# Sheet1.net
KiCad netlist of a schematic drawn in Altium Designer
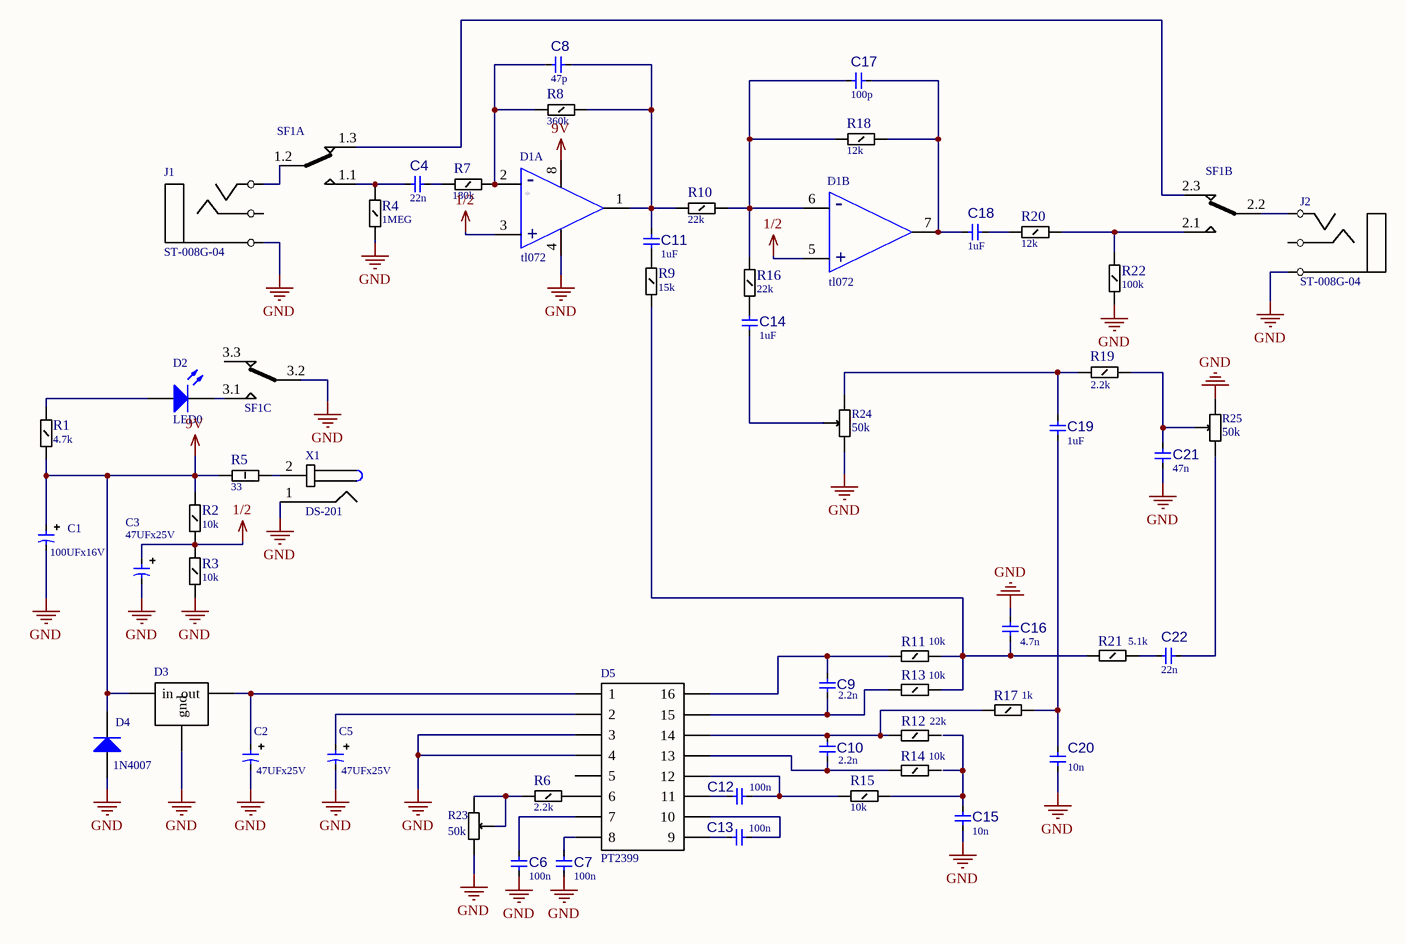
[diagram p0: Sheet1.SchDoc]

(export (version "E")
  (design (tool "Eeschema 10.0.6"))
  (components
    (comp (ref "C1")
      (value "100UFx16V")
      (footprint "C12x5")
      (fields (field (name "PART NUMBER") "Condensator C12x8") (field (name "Comment") "C15x8"))
      (libsource (lib "Database_Libs") (part "C15x8"))
    )
    (comp (ref "C2")
      (value "47UFx25V")
      (footprint "B41828_D5")
      (fields
        (field (name "PART NUMBER") "Condensator B41851")
        (field (name "MANUFACTURER") "Epcos")
        (field (name "Comment") "C15x8")
      )
      (libsource (lib "Database_Libs") (part "C15x8"))
    )
    (comp (ref "C3")
      (value "47UFx25V")
      (footprint "B41828_D5")
      (fields
        (field (name "PART NUMBER") "Condensator B41851")
        (field (name "MANUFACTURER") "Epcos")
        (field (name "Comment") "C15x8")
      )
      (libsource (lib "Database_Libs") (part "C15x8"))
    )
    (comp (ref "C4")
      (value "22n")
      (footprint "B32529C 3222")
      (fields
        (field (name "PART NUMBER") "Condensator C22n")
        (field (name "MANUFACTURERPARTNUMBER") "B32529C1223J000")
        (field (name "Comment") "C0603")
      )
      (libsource (lib "Database_Libs") (part "C0603"))
    )
    (comp (ref "C5")
      (value "47UFx25V")
      (footprint "B41828_D5")
      (fields
        (field (name "PART NUMBER") "Condensator B41851")
        (field (name "MANUFACTURER") "Epcos")
        (field (name "Comment") "C15x8")
      )
      (libsource (lib "Database_Libs") (part "C15x8"))
    )
    (comp (ref "C6")
      (value "100n")
      (footprint "B32529C 3222")
      (fields
        (field (name "PART NUMBER") "Condensator C100n")
        (field (name "MANUFACTURER") "Epcos")
        (field (name "MANUFACTURERPARTNUMBER") "B32529C1223J000")
      )
      (libsource (lib "Database_Libs") (part "C0603"))
    )
    (comp (ref "C7")
      (value "100n")
      (footprint "B32529C 3222")
      (fields
        (field (name "PART NUMBER") "Condensator C100n")
        (field (name "MANUFACTURER") "Epcos")
        (field (name "MANUFACTURERPARTNUMBER") "B32529C1223J000")
      )
      (libsource (lib "Database_Libs") (part "C0603"))
    )
    (comp (ref "C8")
      (value "47p")
      (footprint "C1206")
      (fields (field (name "PART NUMBER") "Condensator 1206 100") (field (name "Comment") "C1206"))
      (libsource (lib "Database_Libs") (part "C1206"))
    )
    (comp (ref "C9")
      (value "2.2n")
      (footprint "B32529C 3222")
      (fields
        (field (name "PART NUMBER") "Condensator C2.2n")
        (field (name "MANUFACTURER") "Китай")
        (field (name "MANUFACTURERPARTNUMBER") "К73-17")
      )
      (libsource (lib "Database_Libs") (part "C0603"))
    )
    (comp (ref "C10")
      (value "2.2n")
      (footprint "B32529C 3222")
      (fields
        (field (name "PART NUMBER") "Condensator C2.2n")
        (field (name "MANUFACTURER") "Китай")
        (field (name "MANUFACTURERPARTNUMBER") "К73-17")
      )
      (libsource (lib "Database_Libs") (part "C0603"))
    )
    (comp (ref "C11")
      (value "1uF")
      (footprint "B32529_C0105")
      (fields
        (field (name "PART NUMBER") "Condensator 1u")
        (field (name "MANUFACTURER") "Epcos")
        (field (name "MANUFACTURERPARTNUMBER") "B32529C0105K000")
      )
      (libsource (lib "Database_Libs") (part "C0603"))
    )
    (comp (ref "C12")
      (value "100n")
      (footprint "B32529C 3222")
      (fields
        (field (name "PART NUMBER") "Condensator C100n")
        (field (name "MANUFACTURER") "Epcos")
        (field (name "MANUFACTURERPARTNUMBER") "B32529C1223J000")
      )
      (libsource (lib "Database_Libs") (part "C0603"))
    )
    (comp (ref "C13")
      (value "100n")
      (footprint "B32529C 3222")
      (fields
        (field (name "PART NUMBER") "Condensator C100n")
        (field (name "MANUFACTURER") "Epcos")
        (field (name "MANUFACTURERPARTNUMBER") "B32529C1223J000")
      )
      (libsource (lib "Database_Libs") (part "C0603"))
    )
    (comp (ref "C14")
      (value "1uF")
      (footprint "B32529_C0105")
      (fields
        (field (name "PART NUMBER") "Condensator 1u")
        (field (name "MANUFACTURER") "Epcos")
        (field (name "MANUFACTURERPARTNUMBER") "B32529C0105K000")
      )
      (libsource (lib "Database_Libs") (part "C0603"))
    )
    (comp (ref "C15")
      (value "10n")
      (footprint "B32529C 3222")
      (fields (field (name "PART NUMBER") "Condensator C10n"))
      (libsource (lib "Database_Libs") (part "C0603"))
    )
    (comp (ref "C16")
      (value "4.7n")
      (footprint "B32529C 3222")
      (fields
        (field (name "PART NUMBER") "Condensator C4.7n")
        (field (name "MANUFACTURER") "Китай")
        (field (name "MANUFACTURERPARTNUMBER") "К73-17")
      )
      (libsource (lib "Database_Libs") (part "C0603"))
    )
    (comp (ref "C17")
      (value "100p")
      (footprint "C1206")
      (fields (field (name "PART NUMBER") "Condensator 1206 100") (field (name "Comment") "C1206"))
      (libsource (lib "Database_Libs") (part "C1206"))
    )
    (comp (ref "C18")
      (value "1uF")
      (footprint "B32529_C0105")
      (fields
        (field (name "PART NUMBER") "Condensator 1u")
        (field (name "MANUFACTURER") "Epcos")
        (field (name "MANUFACTURERPARTNUMBER") "B32529C0105K000")
      )
      (libsource (lib "Database_Libs") (part "C0603"))
    )
    (comp (ref "C19")
      (value "1uF")
      (footprint "B32529_C0105")
      (fields
        (field (name "PART NUMBER") "Condensator 1u")
        (field (name "MANUFACTURER") "Epcos")
        (field (name "MANUFACTURERPARTNUMBER") "B32529C0105K000")
      )
      (libsource (lib "Database_Libs") (part "C0603"))
    )
    (comp (ref "C20")
      (value "10n")
      (footprint "B32529C 3222")
      (fields (field (name "PART NUMBER") "Condensator C10n"))
      (libsource (lib "Database_Libs") (part "C0603"))
    )
    (comp (ref "C21")
      (value "47n")
      (footprint "B32529C 3222")
      (fields
        (field (name "PART NUMBER") "Condensator C47n")
        (field (name "MANUFACTURER") "Epcos")
        (field (name "MANUFACTURERPARTNUMBER") "B32529C1473J000")
      )
      (libsource (lib "Database_Libs") (part "C0603"))
    )
    (comp (ref "C22")
      (value "22n")
      (footprint "B32529C 3222")
      (fields
        (field (name "PART NUMBER") "Condensator C22n")
        (field (name "MANUFACTURERPARTNUMBER") "B32529C1223J000")
        (field (name "Comment") "C0603")
      )
      (libsource (lib "Database_Libs") (part "C0603"))
    )
    (comp (ref "D1") (value "tl072") (footprint "SO8_L") (libsource (lib "Database_Libs") (part "tl072")))
    (comp (ref "D2")
      (value "LED0")
      (footprint "LED-0")
      (description "Typical INFRARED GaAs LED")
      (fields (field (name "PUBLISHER") "Altium Limited"))
      (libsource (lib "Miscellaneous Devices") (part "LED0"))
    )
    (comp (ref "D3")
      (value "L7805")
      (footprint "D2PACK")
      (fields (field (name "MANUFACTURERPARTNUMBER") "L7805ABD2T-TR"))
      (libsource (lib "Database_Libs") (part "L7805"))
    )
    (comp (ref "D4")
      (value "1N4007")
      (footprint "DO-41")
      (description "1 Amp General Purpose Rectifier")
      (fields (field (name "PUBLISHER") "Altium Limited"))
      (libsource (lib "Miscellaneous Devices") (part "Diode 1N4007"))
    )
    (comp (ref "D5")
      (value "PT2399")
      (footprint "DIP-16")
      (fields (field (name "MANUFACTURER") "Princeton Technology"))
      (libsource (lib "Database_Libs") (part "PT2399"))
    )
    (comp (ref "J1")
      (value "ST-008G-04")
      (footprint "ST-008G-04")
      (libsource (lib "Database_Libs") (part "ST-008G-04"))
    )
    (comp (ref "J2")
      (value "ST-008G-04")
      (footprint "ST-008G-04")
      (libsource (lib "Database_Libs") (part "ST-008G-04"))
    )
    (comp (ref "R1")
      (value "4.7k")
      (footprint "R1206")
      (fields (field (name "PART NUMBER") "Resistor 1206 1.5k") (field (name "Comment") "R1206-0,25 W"))
      (libsource (lib "Database_Libs") (part "R1206-0,25 W"))
    )
    (comp (ref "R2")
      (value "10k")
      (footprint "R1206")
      (fields (field (name "PART NUMBER") "Resistor 1206 1.5k") (field (name "Comment") "R1206-0,25 W"))
      (libsource (lib "Database_Libs") (part "R1206-0,25 W"))
    )
    (comp (ref "R3")
      (value "10k")
      (footprint "R1206")
      (fields (field (name "PART NUMBER") "Resistor 1206 1.5k") (field (name "Comment") "R1206-0,25 W"))
      (libsource (lib "Database_Libs") (part "R1206-0,25 W"))
    )
    (comp (ref "R4")
      (value "1MEG")
      (footprint "R1206")
      (fields (field (name "PART NUMBER") "Resistor 1206 300") (field (name "Comment") "R1206-0,25 W"))
      (libsource (lib "Database_Libs") (part "R1206-0,25 W"))
    )
    (comp (ref "R5")
      (value "33")
      (footprint "R2512")
      (fields (field (name "PART NUMBER") "Resistor 2506 33") (field (name "Comment") "R2512-1 W"))
      (libsource (lib "Database_Libs") (part "R2512-1 W"))
    )
    (comp (ref "R6")
      (value "2.2k")
      (footprint "R1206")
      (fields (field (name "PART NUMBER") "Resistor 1206 10k") (field (name "Comment") "R1206-0,25 W"))
      (libsource (lib "Database_Libs") (part "R1206-0,25 W"))
    )
    (comp (ref "R7")
      (value "180k")
      (footprint "R1206")
      (fields (field (name "PART NUMBER") "Resistor 1206 300") (field (name "Comment") "R1206-0,25 W"))
      (libsource (lib "Database_Libs") (part "R1206-0,25 W"))
    )
    (comp (ref "R8")
      (value "360k")
      (footprint "R1206")
      (fields (field (name "PART NUMBER") "Resistor 1206 300") (field (name "Comment") "R1206-0,25 W"))
      (libsource (lib "Database_Libs") (part "R1206-0,25 W"))
    )
    (comp (ref "R9")
      (value "15k")
      (footprint "R1206")
      (fields (field (name "PART NUMBER") "Resistor 1206 300") (field (name "Comment") "R1206-0,25 W"))
      (libsource (lib "Database_Libs") (part "R1206-0,25 W"))
    )
    (comp (ref "R10")
      (value "22k")
      (footprint "R1206")
      (fields (field (name "PART NUMBER") "Resistor 1206 300") (field (name "Comment") "R1206-0,25 W"))
      (libsource (lib "Database_Libs") (part "R1206-0,25 W"))
    )
    (comp (ref "R11")
      (value "10k")
      (footprint "R1206")
      (fields (field (name "PART NUMBER") "Resistor 1206 10k") (field (name "Comment") "R1206-0,25 W"))
      (libsource (lib "Database_Libs") (part "R1206-0,25 W"))
    )
    (comp (ref "R12")
      (value "22k")
      (footprint "R1206")
      (fields (field (name "PART NUMBER") "Resistor 1206 10k") (field (name "Comment") "R1206-0,25 W"))
      (libsource (lib "Database_Libs") (part "R1206-0,25 W"))
    )
    (comp (ref "R13")
      (value "10k")
      (footprint "R1206")
      (fields (field (name "PART NUMBER") "Resistor 1206 10k") (field (name "Comment") "R1206-0,25 W"))
      (libsource (lib "Database_Libs") (part "R1206-0,25 W"))
    )
    (comp (ref "R14")
      (value "10k")
      (footprint "R1206")
      (fields (field (name "PART NUMBER") "Resistor 1206 10k") (field (name "Comment") "R1206-0,25 W"))
      (libsource (lib "Database_Libs") (part "R1206-0,25 W"))
    )
    (comp (ref "R15")
      (value "10k")
      (footprint "R1206")
      (fields (field (name "PART NUMBER") "Resistor 1206 10k") (field (name "Comment") "R1206-0,25 W"))
      (libsource (lib "Database_Libs") (part "R1206-0,25 W"))
    )
    (comp (ref "R16")
      (value "22k")
      (footprint "R1206")
      (fields (field (name "PART NUMBER") "Resistor 1206 300") (field (name "Comment") "R1206-0,25 W"))
      (libsource (lib "Database_Libs") (part "R1206-0,25 W"))
    )
    (comp (ref "R17")
      (value "1k")
      (footprint "R1206")
      (fields (field (name "PART NUMBER") "Resistor 1206 10k") (field (name "Comment") "R1206-0,25 W"))
      (libsource (lib "Database_Libs") (part "R1206-0,25 W"))
    )
    (comp (ref "R18")
      (value "12k")
      (footprint "R1206")
      (fields (field (name "PART NUMBER") "Resistor 1206 300") (field (name "Comment") "R1206-0,25 W"))
      (libsource (lib "Database_Libs") (part "R1206-0,25 W"))
    )
    (comp (ref "R19")
      (value "2.2k")
      (footprint "R1206")
      (fields (field (name "PART NUMBER") "Resistor 1206 300") (field (name "Comment") "R1206-0,25 W"))
      (libsource (lib "Database_Libs") (part "R1206-0,25 W"))
    )
    (comp (ref "R20")
      (value "12k")
      (footprint "R1206")
      (fields (field (name "PART NUMBER") "Resistor 1206 300") (field (name "Comment") "R1206-0,25 W"))
      (libsource (lib "Database_Libs") (part "R1206-0,25 W"))
    )
    (comp (ref "R21")
      (value "5.1k")
      (footprint "R1206")
      (fields (field (name "PART NUMBER") "Resistor 1206 10k") (field (name "Comment") "R1206-0,25 W"))
      (libsource (lib "Database_Libs") (part "R1206-0,25 W"))
    )
    (comp (ref "R22")
      (value "100k")
      (footprint "R1206")
      (fields (field (name "PART NUMBER") "Resistor 1206 300") (field (name "Comment") "R1206-0,25 W"))
      (libsource (lib "Database_Libs") (part "R1206-0,25 W"))
    )
    (comp (ref "R23")
      (value "50k")
      (footprint "16K1")
      (fields (field (name "PART NUMBER") "Resistor 16K1"))
      (libsource (lib "Database_Libs") (part "16K1"))
    )
    (comp (ref "R24")
      (value "50k")
      (footprint "16K1")
      (fields (field (name "PART NUMBER") "Resistor 16K1"))
      (libsource (lib "Database_Libs") (part "16K1"))
    )
    (comp (ref "R25")
      (value "50k")
      (footprint "16K1")
      (fields (field (name "PART NUMBER") "Resistor 16K1"))
      (libsource (lib "Database_Libs") (part "16K1"))
    )
    (comp (ref "SF1")
      (value "SF-17020F-0302-21R-L")
      (footprint "SF-17020F-0302-21R-L")
      (fields (field (name "PART NUMBER") "SF-17020F"))
      (libsource (lib "") (part "SF-17020F-0302-21R-L_1"))
    )
    (comp (ref "X1") (value "DS-201") (footprint "DS-201") (libsource (lib "Database_Libs") (part "DS-201")))
  )
  (nets
    (net (code "1") (name "1{slash}2") (class "Default")
      (node (ref "C3") (pin "1") (pinfunction "1_1") (pintype "passive"))
      (node (ref "D1") (pin "3") (pinfunction "3_3") (pintype "passive"))
      (node (ref "D1") (pin "5") (pinfunction "5_5") (pintype "passive"))
      (node (ref "R2") (pin "1") (pinfunction "1_1") (pintype "passive"))
      (node (ref "R3") (pin "2") (pinfunction "2_2") (pintype "passive"))
    )
    (net (code "2") (name "9V") (class "Default")
      (node (ref "C1") (pin "1") (pinfunction "1_1") (pintype "passive"))
      (node (ref "D1") (pin "8") (pinfunction "8_8") (pintype "passive"))
      (node (ref "D3") (pin "1") (pinfunction "in_1") (pintype "passive"))
      (node (ref "D4") (pin "2") (pinfunction "K_2") (pintype "passive"))
      (node (ref "R1") (pin "1") (pinfunction "1_1") (pintype "passive"))
      (node (ref "R2") (pin "2") (pinfunction "2_2") (pintype "passive"))
      (node (ref "R5") (pin "1") (pinfunction "1_1") (pintype "passive"))
    )
    (net (code "3") (name "GND") (class "Default")
      (node (ref "C1") (pin "2") (pinfunction "2_2") (pintype "passive"))
      (node (ref "C15") (pin "1") (pinfunction "1_1") (pintype "passive"))
      (node (ref "C16") (pin "2") (pinfunction "2_2") (pintype "passive"))
      (node (ref "C2") (pin "2") (pinfunction "2_2") (pintype "passive"))
      (node (ref "C20") (pin "1") (pinfunction "1_1") (pintype "passive"))
      (node (ref "C21") (pin "1") (pinfunction "1_1") (pintype "passive"))
      (node (ref "C3") (pin "2") (pinfunction "2_2") (pintype "passive"))
      (node (ref "C5") (pin "2") (pinfunction "2_2") (pintype "passive"))
      (node (ref "C6") (pin "1") (pinfunction "1_1") (pintype "passive"))
      (node (ref "C7") (pin "1") (pinfunction "1_1") (pintype "passive"))
      (node (ref "D1") (pin "4") (pinfunction "4_4") (pintype "passive"))
      (node (ref "D3") (pin "0") (pinfunction "gnd_0") (pintype "passive"))
      (node (ref "D4") (pin "1") (pinfunction "A_1") (pintype "passive"))
      (node (ref "D5") (pin "3") (pinfunction "3_3") (pintype "passive"))
      (node (ref "D5") (pin "4") (pinfunction "4_4") (pintype "passive"))
      (node (ref "J1") (pin "3") (pinfunction "3_3") (pintype "passive"))
      (node (ref "J2") (pin "3") (pinfunction "3_3") (pintype "passive"))
      (node (ref "R22") (pin "1") (pinfunction "1_1") (pintype "passive"))
      (node (ref "R23") (pin "1") (pinfunction "1_1") (pintype "passive"))
      (node (ref "R24") (pin "3") (pinfunction "3_3") (pintype "passive"))
      (node (ref "R25") (pin "1") (pinfunction "1_1") (pintype "passive"))
      (node (ref "R3") (pin "1") (pinfunction "1_1") (pintype "passive"))
      (node (ref "R4") (pin "1") (pinfunction "1_1") (pintype "passive"))
      (node (ref "SF1") (pin "3.2") (pinfunction "3.2_3.2") (pintype "passive"))
      (node (ref "X1") (pin "1") (pinfunction "1_1") (pintype "passive"))
    )
    (net (code "4") (name "Net-(C4-Pad1)") (class "Default")
      (node (ref "C4") (pin "1") (pinfunction "1_1") (pintype "passive"))
      (node (ref "R4") (pin "2") (pinfunction "2_2") (pintype "passive"))
      (node (ref "SF1") (pin "1.1") (pinfunction "1.1_1.1") (pintype "passive"))
    )
    (net (code "5") (name "Net-(C4-Pad2)") (class "Default")
      (node (ref "C4") (pin "2") (pinfunction "2_2") (pintype "passive"))
      (node (ref "R7") (pin "1") (pinfunction "1_1") (pintype "passive"))
    )
    (net (code "6") (name "Net-(C5-Pad1)") (class "Default")
      (node (ref "C5") (pin "1") (pinfunction "1_1") (pintype "passive"))
      (node (ref "D5") (pin "2") (pinfunction "2_2") (pintype "passive"))
    )
    (net (code "7") (name "Net-(C6-Pad2)") (class "Default")
      (node (ref "C6") (pin "2") (pinfunction "2_2") (pintype "passive"))
      (node (ref "D5") (pin "7") (pinfunction "7_7") (pintype "passive"))
    )
    (net (code "8") (name "Net-(C7-Pad2)") (class "Default")
      (node (ref "C7") (pin "2") (pinfunction "2_2") (pintype "passive"))
      (node (ref "D5") (pin "8") (pinfunction "8_8") (pintype "passive"))
    )
    (net (code "9") (name "Net-(C8-Pad1)") (class "Default")
      (node (ref "C8") (pin "1") (pinfunction "1_1") (pintype "passive"))
      (node (ref "D1") (pin "2") (pinfunction "2_2") (pintype "passive"))
      (node (ref "R7") (pin "2") (pinfunction "2_2") (pintype "passive"))
      (node (ref "R8") (pin "1") (pinfunction "1_1") (pintype "passive"))
    )
    (net (code "10") (name "Net-(C9-Pad1)") (class "Default")
      (node (ref "C9") (pin "1") (pinfunction "1_1") (pintype "passive"))
      (node (ref "D5") (pin "16") (pinfunction "16_16") (pintype "passive"))
      (node (ref "R11") (pin "1") (pinfunction "1_1") (pintype "passive"))
    )
    (net (code "11") (name "Net-(C9-Pad2)") (class "Default")
      (node (ref "C9") (pin "2") (pinfunction "2_2") (pintype "passive"))
      (node (ref "D5") (pin "15") (pinfunction "15_15") (pintype "passive"))
      (node (ref "R13") (pin "1") (pinfunction "1_1") (pintype "passive"))
    )
    (net (code "12") (name "Net-(C10-Pad1)") (class "Default")
      (node (ref "C10") (pin "1") (pinfunction "1_1") (pintype "passive"))
      (node (ref "D5") (pin "14") (pinfunction "14_14") (pintype "passive"))
      (node (ref "R12") (pin "1") (pinfunction "1_1") (pintype "passive"))
      (node (ref "R17") (pin "1") (pinfunction "1_1") (pintype "passive"))
    )
    (net (code "13") (name "Net-(C10-Pad2)") (class "Default")
      (node (ref "C10") (pin "2") (pinfunction "2_2") (pintype "passive"))
      (node (ref "D5") (pin "13") (pinfunction "13_13") (pintype "passive"))
      (node (ref "R14") (pin "1") (pinfunction "1_1") (pintype "passive"))
    )
    (net (code "14") (name "Net-(C11-Pad1)") (class "Default")
      (node (ref "C11") (pin "1") (pinfunction "1_1") (pintype "passive"))
      (node (ref "R9") (pin "2") (pinfunction "2_2") (pintype "passive"))
    )
    (net (code "15") (name "Net-(C11-Pad2)") (class "Default")
      (node (ref "C11") (pin "2") (pinfunction "2_2") (pintype "passive"))
      (node (ref "C8") (pin "2") (pinfunction "2_2") (pintype "passive"))
      (node (ref "D1") (pin "1") (pinfunction "1_1") (pintype "passive"))
      (node (ref "R10") (pin "1") (pinfunction "1_1") (pintype "passive"))
      (node (ref "R8") (pin "2") (pinfunction "2_2") (pintype "passive"))
    )
    (net (code "16") (name "Net-(C12-Pad1)") (class "Default")
      (node (ref "C12") (pin "1") (pinfunction "1_1") (pintype "passive"))
      (node (ref "D5") (pin "12") (pinfunction "12_12") (pintype "passive"))
      (node (ref "R15") (pin "1") (pinfunction "1_1") (pintype "passive"))
    )
    (net (code "17") (name "Net-(C12-Pad2)") (class "Default")
      (node (ref "C12") (pin "2") (pinfunction "2_2") (pintype "passive"))
      (node (ref "D5") (pin "11") (pinfunction "11_11") (pintype "passive"))
    )
    (net (code "18") (name "Net-(C13-Pad1)") (class "Default")
      (node (ref "C13") (pin "1") (pinfunction "1_1") (pintype "passive"))
      (node (ref "D5") (pin "10") (pinfunction "10_10") (pintype "passive"))
    )
    (net (code "19") (name "Net-(C13-Pad2)") (class "Default")
      (node (ref "C13") (pin "2") (pinfunction "2_2") (pintype "passive"))
      (node (ref "D5") (pin "9") (pinfunction "9_9") (pintype "passive"))
    )
    (net (code "20") (name "Net-(C14-Pad1)") (class "Default")
      (node (ref "C14") (pin "1") (pinfunction "1_1") (pintype "passive"))
      (node (ref "R24") (pin "2") (pinfunction "2_2") (pintype "passive"))
    )
    (net (code "21") (name "Net-(C14-Pad2)") (class "Default")
      (node (ref "C14") (pin "2") (pinfunction "2_2") (pintype "passive"))
      (node (ref "R16") (pin "1") (pinfunction "1_1") (pintype "passive"))
    )
    (net (code "22") (name "Net-(C15-Pad2)") (class "Default")
      (node (ref "C15") (pin "2") (pinfunction "2_2") (pintype "passive"))
      (node (ref "R15") (pin "2") (pinfunction "2_2") (pintype "passive"))
    )
    (net (code "23") (name "Net-(C16-Pad1)") (class "Default")
      (node (ref "C16") (pin "1") (pinfunction "1_1") (pintype "passive"))
      (node (ref "R11") (pin "2") (pinfunction "2_2") (pintype "passive"))
      (node (ref "R13") (pin "2") (pinfunction "2_2") (pintype "passive"))
      (node (ref "R21") (pin "1") (pinfunction "1_1") (pintype "passive"))
      (node (ref "R9") (pin "1") (pinfunction "1_1") (pintype "passive"))
    )
    (net (code "24") (name "Net-(C17-Pad1)") (class "Default")
      (node (ref "C17") (pin "1") (pinfunction "1_1") (pintype "passive"))
      (node (ref "D1") (pin "6") (pinfunction "6_6") (pintype "passive"))
      (node (ref "R10") (pin "2") (pinfunction "2_2") (pintype "passive"))
      (node (ref "R16") (pin "2") (pinfunction "2_2") (pintype "passive"))
      (node (ref "R18") (pin "1") (pinfunction "1_1") (pintype "passive"))
    )
    (net (code "25") (name "Net-(C17-Pad2)") (class "Default")
      (node (ref "C17") (pin "2") (pinfunction "2_2") (pintype "passive"))
      (node (ref "C18") (pin "2") (pinfunction "2_2") (pintype "passive"))
      (node (ref "D1") (pin "7") (pinfunction "7_7") (pintype "passive"))
      (node (ref "R18") (pin "2") (pinfunction "2_2") (pintype "passive"))
    )
    (net (code "26") (name "Net-(C18-Pad1)") (class "Default")
      (node (ref "C18") (pin "1") (pinfunction "1_1") (pintype "passive"))
      (node (ref "R20") (pin "1") (pinfunction "1_1") (pintype "passive"))
    )
    (net (code "27") (name "Net-(C19-Pad1)") (class "Default")
      (node (ref "C19") (pin "1") (pinfunction "1_1") (pintype "passive"))
      (node (ref "C20") (pin "2") (pinfunction "2_2") (pintype "passive"))
      (node (ref "R17") (pin "2") (pinfunction "2_2") (pintype "passive"))
    )
    (net (code "28") (name "Net-(C19-Pad2)") (class "Default")
      (node (ref "C19") (pin "2") (pinfunction "2_2") (pintype "passive"))
      (node (ref "R19") (pin "1") (pinfunction "1_1") (pintype "passive"))
      (node (ref "R24") (pin "1") (pinfunction "1_1") (pintype "passive"))
    )
    (net (code "29") (name "Net-(C21-Pad2)") (class "Default")
      (node (ref "C21") (pin "2") (pinfunction "2_2") (pintype "passive"))
      (node (ref "R19") (pin "2") (pinfunction "2_2") (pintype "passive"))
      (node (ref "R25") (pin "2") (pinfunction "2_2") (pintype "passive"))
    )
    (net (code "30") (name "Net-(C22-Pad1)") (class "Default")
      (node (ref "C22") (pin "1") (pinfunction "1_1") (pintype "passive"))
      (node (ref "R21") (pin "2") (pinfunction "2_2") (pintype "passive"))
    )
    (net (code "31") (name "Net-(C22-Pad2)") (class "Default")
      (node (ref "C22") (pin "2") (pinfunction "2_2") (pintype "passive"))
      (node (ref "R25") (pin "3") (pinfunction "3_3") (pintype "passive"))
    )
    (net (code "32") (name "Net-(D2-A)") (class "Default")
      (node (ref "D2") (pin "1") (pinfunction "A_1") (pintype "passive"))
      (node (ref "R1") (pin "2") (pinfunction "2_2") (pintype "passive"))
    )
    (net (code "33") (name "Net-(D2-K)") (class "Default")
      (node (ref "D2") (pin "2") (pinfunction "K_2") (pintype "passive"))
      (node (ref "SF1") (pin "3.1") (pinfunction "3.1_3.1") (pintype "passive"))
    )
    (net (code "34") (name "Net-(D3-out)") (class "Default")
      (node (ref "C2") (pin "1") (pinfunction "1_1") (pintype "passive"))
      (node (ref "D3") (pin "2") (pinfunction "out_2") (pintype "passive"))
      (node (ref "D5") (pin "1") (pinfunction "1_1") (pintype "passive"))
    )
    (net (code "35") (name "Net-(D5-Pad6)") (class "Default")
      (node (ref "D5") (pin "6") (pinfunction "6_6") (pintype "passive"))
      (node (ref "R6") (pin "2") (pinfunction "2_2") (pintype "passive"))
    )
    (net (code "36") (name "Net-(J1-Pad2)") (class "Default")
      (node (ref "J1") (pin "2") (pinfunction "2_2") (pintype "passive"))
      (node (ref "SF1") (pin "1.2") (pinfunction "1.2_1.2") (pintype "passive"))
    )
    (net (code "37") (name "Net-(J2-Pad2)") (class "Default")
      (node (ref "J2") (pin "2") (pinfunction "2_2") (pintype "passive"))
      (node (ref "SF1") (pin "2.2") (pinfunction "2.2_2.2") (pintype "passive"))
    )
    (net (code "38") (name "Net-(R5-Pad2)") (class "Default")
      (node (ref "R5") (pin "2") (pinfunction "2_2") (pintype "passive"))
      (node (ref "X1") (pin "2") (pinfunction "2_2") (pintype "passive"))
    )
    (net (code "39") (name "Net-(R20-Pad2)") (class "Default")
      (node (ref "R20") (pin "2") (pinfunction "2_2") (pintype "passive"))
      (node (ref "R22") (pin "2") (pinfunction "2_2") (pintype "passive"))
      (node (ref "SF1") (pin "2.1") (pinfunction "2.1_2.1") (pintype "passive"))
    )
    (net (code "40") (name "Net-(R23-Pad2)") (class "Default")
      (node (ref "R23") (pin "2") (pinfunction "2_2") (pintype "passive"))
      (node (ref "R23") (pin "3") (pinfunction "3_3") (pintype "passive"))
      (node (ref "R6") (pin "1") (pinfunction "1_1") (pintype "passive"))
    )
    (net (code "41") (name "Net-(SF1-Pad1.3)") (class "Default")
      (node (ref "SF1") (pin "1.3") (pinfunction "1.3_1.3") (pintype "passive"))
      (node (ref "SF1") (pin "2.3") (pinfunction "2.3_2.3") (pintype "passive"))
    )
    (net (code "42") (name "unconnected-(D5-Pad5)") (class "Default")
      (node (ref "D5") (pin "5") (pinfunction "5_5") (pintype "passive"))
    )
    (net (code "43") (name "unconnected-(J1-Pad1)") (class "Default")
      (node (ref "J1") (pin "1") (pinfunction "1_1") (pintype "passive"))
    )
    (net (code "44") (name "unconnected-(J2-Pad1)") (class "Default")
      (node (ref "J2") (pin "1") (pinfunction "1_1") (pintype "passive"))
    )
    (net (code "45") (name "unconnected-(R12-Pad2)") (class "Default")
      (node (ref "R12") (pin "2") (pinfunction "2_2") (pintype "passive"))
    )
    (net (code "46") (name "unconnected-(R14-Pad2)") (class "Default")
      (node (ref "R14") (pin "2") (pinfunction "2_2") (pintype "passive"))
    )
    (net (code "47") (name "unconnected-(SF1C-1.3-Pad3.3)") (class "Default")
      (node (ref "SF1") (pin "3.3") (pinfunction "1.3_3.3") (pintype "passive"))
    )
  )
)
